# FXAS21002C.net
KiCad netlist of a schematic drawn in Altium Designer
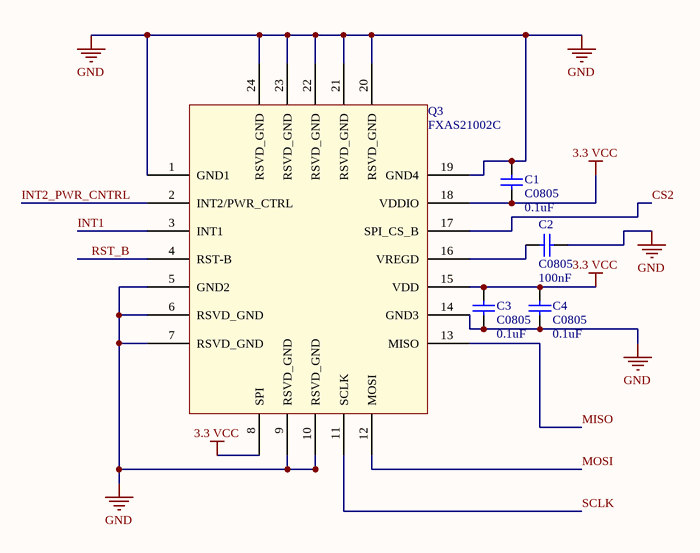
[diagram p0: FXAS21002C.SchDoc]

(export (version "E")
  (design (tool "Eeschema 10.0.6"))
  (components
    (comp (ref "C1")
      (value "C0805")
      (footprint "0805")
      (description "Ceramic Chip Capacitor - Standard")
      (fields (field (name "ALTIUM_VALUE") "0.1uF") (field (name "PUBLISHER") "Altium Limited"))
      (libsource (lib "KEMET Chip Capacitor") (part "C0805"))
    )
    (comp (ref "C2")
      (value "C0805")
      (footprint "0805")
      (description "Ceramic Chip Capacitor - Standard")
      (fields (field (name "ALTIUM_VALUE") "100nF") (field (name "PUBLISHER") "Altium Limited"))
      (libsource (lib "KEMET Chip Capacitor") (part "C0805"))
    )
    (comp (ref "C3")
      (value "C0805")
      (footprint "0805")
      (description "Ceramic Chip Capacitor - Standard")
      (fields (field (name "ALTIUM_VALUE") "0.1uF") (field (name "PUBLISHER") "Altium Limited"))
      (libsource (lib "KEMET Chip Capacitor") (part "C0805"))
    )
    (comp (ref "C4")
      (value "C0805")
      (footprint "0805")
      (description "Ceramic Chip Capacitor - Standard")
      (fields (field (name "ALTIUM_VALUE") "0.1uF") (field (name "PUBLISHER") "Altium Limited"))
      (libsource (lib "KEMET Chip Capacitor") (part "C0805"))
    )
    (comp (ref "Q3")
      (value "FXAS21002C")
      (footprint "FXAS21002C-24QFN")
      (libsource (lib "FXAS21002C") (part "FXAS21002C"))
    )
  )
  (nets
    (net (code "1") (name "/CS2") (class "Default")
      (node (ref "Q3") (pin "17") (pinfunction "SPI_CS_B_17") (pintype "passive"))
    )
    (net (code "2") (name "/INT1") (class "Default")
      (node (ref "Q3") (pin "3") (pinfunction "INT1_3") (pintype "passive"))
    )
    (net (code "3") (name "/INT2_PWR_CNTRL") (class "Default")
      (node (ref "Q3") (pin "2") (pinfunction "INT2/PWR_CTRL_2") (pintype "passive"))
    )
    (net (code "4") (name "/MISO") (class "Default")
      (node (ref "Q3") (pin "13") (pinfunction "MISO_13") (pintype "passive"))
    )
    (net (code "5") (name "/MOSI") (class "Default")
      (node (ref "Q3") (pin "12") (pinfunction "MOSI_12") (pintype "passive"))
    )
    (net (code "6") (name "/RST_B") (class "Default")
      (node (ref "Q3") (pin "4") (pinfunction "RST-B_4") (pintype "passive"))
    )
    (net (code "7") (name "/SCLK") (class "Default")
      (node (ref "Q3") (pin "11") (pinfunction "SCLK_11") (pintype "passive"))
    )
    (net (code "8") (name "3.3 VCC") (class "Default")
      (node (ref "C1") (pin "1") (pinfunction "1_1") (pintype "passive"))
      (node (ref "C3") (pin "2") (pinfunction "2_2") (pintype "passive"))
      (node (ref "C4") (pin "2") (pinfunction "2_2") (pintype "passive"))
      (node (ref "Q3") (pin "15") (pinfunction "VDD_15") (pintype "passive"))
      (node (ref "Q3") (pin "18") (pinfunction "VDDIO_18") (pintype "passive"))
      (node (ref "Q3") (pin "8") (pinfunction "SPI_8") (pintype "passive"))
    )
    (net (code "9") (name "GND") (class "Default")
      (node (ref "C1") (pin "2") (pinfunction "2_2") (pintype "passive"))
      (node (ref "C2") (pin "2") (pinfunction "2_2") (pintype "passive"))
      (node (ref "C3") (pin "1") (pinfunction "1_1") (pintype "passive"))
      (node (ref "C4") (pin "1") (pinfunction "1_1") (pintype "passive"))
      (node (ref "Q3") (pin "1") (pinfunction "GND1_1") (pintype "passive"))
      (node (ref "Q3") (pin "10") (pinfunction "RSVD_GND_10") (pintype "passive"))
      (node (ref "Q3") (pin "14") (pinfunction "GND3_14") (pintype "passive"))
      (node (ref "Q3") (pin "19") (pinfunction "GND4_19") (pintype "passive"))
      (node (ref "Q3") (pin "20") (pinfunction "RSVD_GND_20") (pintype "passive"))
      (node (ref "Q3") (pin "21") (pinfunction "RSVD_GND_21") (pintype "passive"))
      (node (ref "Q3") (pin "22") (pinfunction "RSVD_GND_22") (pintype "passive"))
      (node (ref "Q3") (pin "23") (pinfunction "RSVD_GND_23") (pintype "passive"))
      (node (ref "Q3") (pin "24") (pinfunction "RSVD_GND_24") (pintype "passive"))
      (node (ref "Q3") (pin "5") (pinfunction "GND2_5") (pintype "passive"))
      (node (ref "Q3") (pin "6") (pinfunction "RSVD_GND_6") (pintype "passive"))
      (node (ref "Q3") (pin "7") (pinfunction "RSVD_GND_7") (pintype "passive"))
      (node (ref "Q3") (pin "9") (pinfunction "RSVD_GND_9") (pintype "passive"))
    )
    (net (code "10") (name "Net-(Q3-VREGD)") (class "Default")
      (node (ref "C2") (pin "1") (pinfunction "1_1") (pintype "passive"))
      (node (ref "Q3") (pin "16") (pinfunction "VREGD_16") (pintype "passive"))
    )
  )
)
